# Audio.net
KiCad netlist of a schematic drawn in Altium Designer
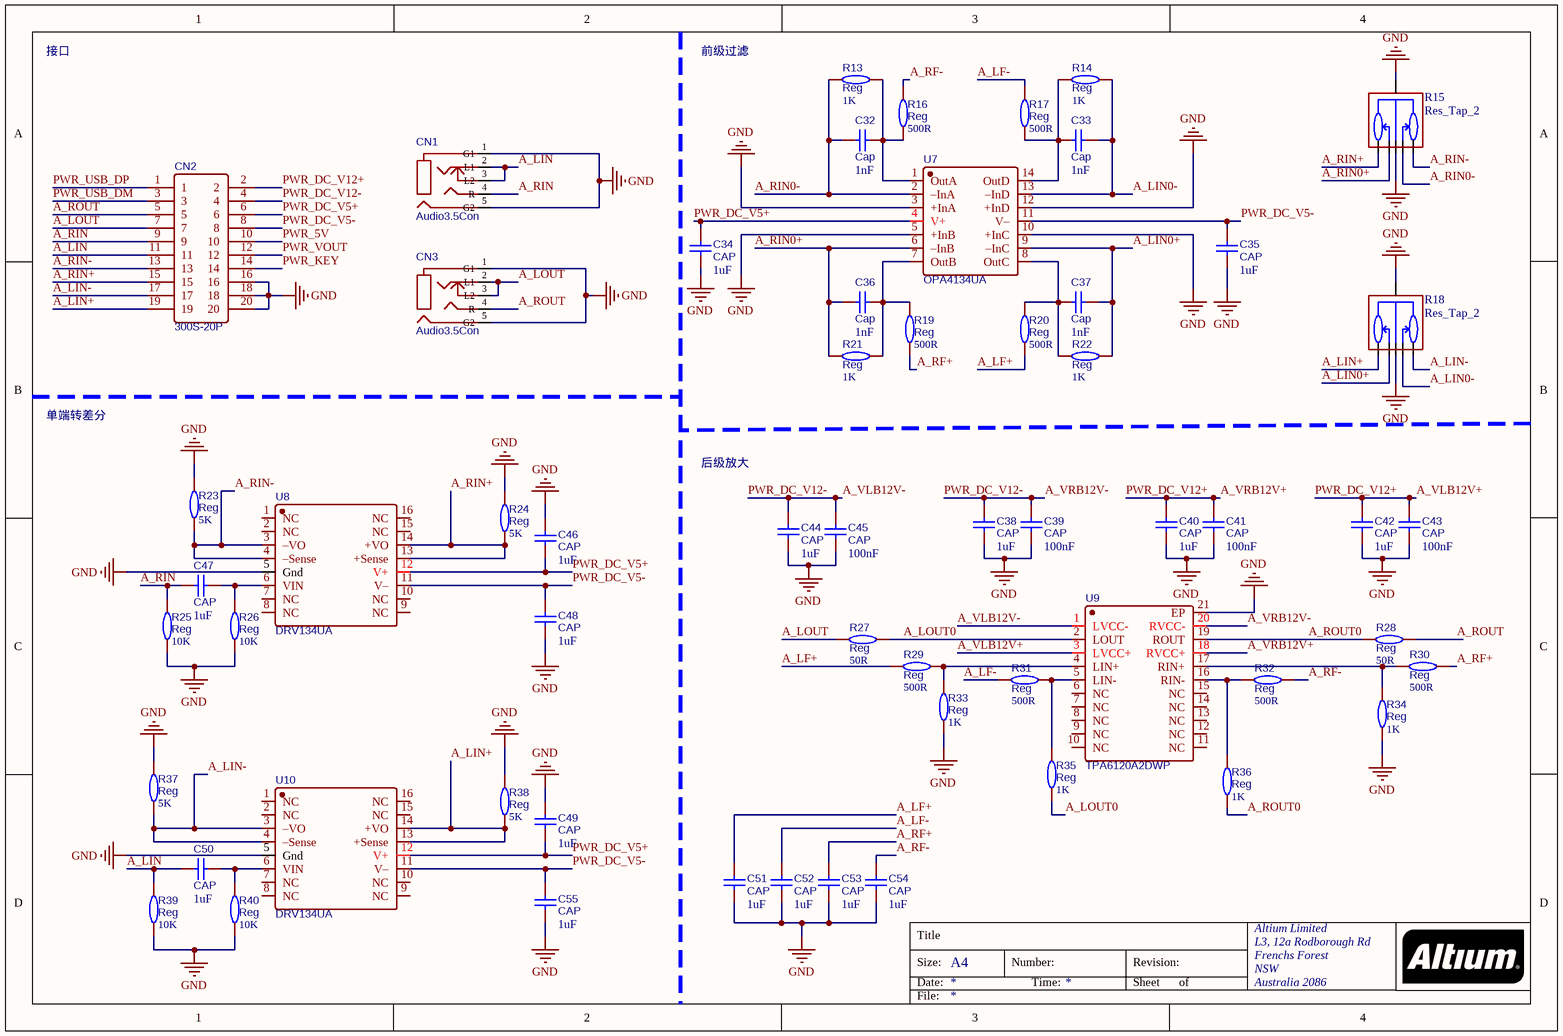
[diagram p0: Audio.SchDoc]

(export (version "E")
  (design (tool "Eeschema 10.0.6"))
  (components
    (comp (ref "C32")
      (value "Cap")
      (footprint "C0603")
      (fields
        (field (name "BOM_SUPPLIER PART") "C302008")
        (field (name "BOM_MANUFACTURER PART") "0603B103K101CT")
        (field (name "ALTIUM_VALUE") "1nF")
        (field (name "CONTRIBUTOR") "LCSC")
      )
      (libsource (lib "Levent_lib") (part "CAP"))
    )
    (comp (ref "C33")
      (value "Cap")
      (footprint "C0603")
      (fields
        (field (name "BOM_SUPPLIER PART") "C302008")
        (field (name "BOM_MANUFACTURER PART") "0603B103K101CT")
        (field (name "ALTIUM_VALUE") "1nF")
        (field (name "CONTRIBUTOR") "LCSC")
      )
      (libsource (lib "Levent_lib") (part "CAP"))
    )
    (comp (ref "C34")
      (value "CAP")
      (footprint "C0603")
      (description "Cap")
      (fields
        (field (name "BOM_SUPPLIER PART") "C302008")
        (field (name "BOM_MANUFACTURER PART") "0603B103K101CT")
        (field (name "ALTIUM_VALUE") "1uF")
        (field (name "CONTRIBUTOR") "LCSC")
      )
      (libsource (lib "Levent_lib") (part "CAP"))
    )
    (comp (ref "C35")
      (value "CAP")
      (footprint "C0603")
      (description "Cap")
      (fields
        (field (name "BOM_SUPPLIER PART") "C302008")
        (field (name "BOM_MANUFACTURER PART") "0603B103K101CT")
        (field (name "ALTIUM_VALUE") "1uF")
        (field (name "CONTRIBUTOR") "LCSC")
      )
      (libsource (lib "Levent_lib") (part "CAP"))
    )
    (comp (ref "C36")
      (value "Cap")
      (footprint "C0603")
      (fields
        (field (name "BOM_SUPPLIER PART") "C302008")
        (field (name "BOM_MANUFACTURER PART") "0603B103K101CT")
        (field (name "ALTIUM_VALUE") "1nF")
        (field (name "CONTRIBUTOR") "LCSC")
      )
      (libsource (lib "Levent_lib") (part "CAP"))
    )
    (comp (ref "C37")
      (value "Cap")
      (footprint "C0603")
      (fields
        (field (name "BOM_SUPPLIER PART") "C302008")
        (field (name "BOM_MANUFACTURER PART") "0603B103K101CT")
        (field (name "ALTIUM_VALUE") "1nF")
        (field (name "CONTRIBUTOR") "LCSC")
      )
      (libsource (lib "Levent_lib") (part "CAP"))
    )
    (comp (ref "C38")
      (value "CAP")
      (footprint "C0603")
      (description "Cap")
      (fields
        (field (name "BOM_SUPPLIER PART") "C302008")
        (field (name "BOM_MANUFACTURER PART") "0603B103K101CT")
        (field (name "ALTIUM_VALUE") "1uF")
        (field (name "CONTRIBUTOR") "LCSC")
      )
      (libsource (lib "Levent_lib") (part "CAP"))
    )
    (comp (ref "C39")
      (value "CAP")
      (footprint "C0603")
      (description "Cap")
      (fields
        (field (name "BOM_SUPPLIER PART") "C302008")
        (field (name "BOM_MANUFACTURER PART") "0603B103K101CT")
        (field (name "ALTIUM_VALUE") "100nF")
        (field (name "CONTRIBUTOR") "LCSC")
      )
      (libsource (lib "Levent_lib") (part "CAP"))
    )
    (comp (ref "C40")
      (value "CAP")
      (footprint "C0603")
      (description "Cap")
      (fields
        (field (name "BOM_SUPPLIER PART") "C302008")
        (field (name "BOM_MANUFACTURER PART") "0603B103K101CT")
        (field (name "ALTIUM_VALUE") "1uF")
        (field (name "CONTRIBUTOR") "LCSC")
      )
      (libsource (lib "Levent_lib") (part "CAP"))
    )
    (comp (ref "C41")
      (value "CAP")
      (footprint "C0603")
      (description "Cap")
      (fields
        (field (name "BOM_SUPPLIER PART") "C302008")
        (field (name "BOM_MANUFACTURER PART") "0603B103K101CT")
        (field (name "ALTIUM_VALUE") "100nF")
        (field (name "CONTRIBUTOR") "LCSC")
      )
      (libsource (lib "Levent_lib") (part "CAP"))
    )
    (comp (ref "C42")
      (value "CAP")
      (footprint "C0603")
      (description "Cap")
      (fields
        (field (name "BOM_SUPPLIER PART") "C302008")
        (field (name "BOM_MANUFACTURER PART") "0603B103K101CT")
        (field (name "ALTIUM_VALUE") "1uF")
        (field (name "CONTRIBUTOR") "LCSC")
      )
      (libsource (lib "Levent_lib") (part "CAP"))
    )
    (comp (ref "C43")
      (value "CAP")
      (footprint "C0603")
      (description "Cap")
      (fields
        (field (name "BOM_SUPPLIER PART") "C302008")
        (field (name "BOM_MANUFACTURER PART") "0603B103K101CT")
        (field (name "ALTIUM_VALUE") "100nF")
        (field (name "CONTRIBUTOR") "LCSC")
      )
      (libsource (lib "Levent_lib") (part "CAP"))
    )
    (comp (ref "C44")
      (value "CAP")
      (footprint "C0603")
      (description "Cap")
      (fields
        (field (name "BOM_SUPPLIER PART") "C302008")
        (field (name "BOM_MANUFACTURER PART") "0603B103K101CT")
        (field (name "ALTIUM_VALUE") "1uF")
        (field (name "CONTRIBUTOR") "LCSC")
      )
      (libsource (lib "Levent_lib") (part "CAP"))
    )
    (comp (ref "C45")
      (value "CAP")
      (footprint "C0603")
      (description "Cap")
      (fields
        (field (name "BOM_SUPPLIER PART") "C302008")
        (field (name "BOM_MANUFACTURER PART") "0603B103K101CT")
        (field (name "ALTIUM_VALUE") "100nF")
        (field (name "CONTRIBUTOR") "LCSC")
      )
      (libsource (lib "Levent_lib") (part "CAP"))
    )
    (comp (ref "C46")
      (value "CAP")
      (footprint "C0603")
      (description "Cap")
      (fields
        (field (name "BOM_SUPPLIER PART") "C302008")
        (field (name "BOM_MANUFACTURER PART") "0603B103K101CT")
        (field (name "ALTIUM_VALUE") "1uF")
        (field (name "CONTRIBUTOR") "LCSC")
      )
      (libsource (lib "Levent_lib") (part "CAP"))
    )
    (comp (ref "C47")
      (value "CAP")
      (footprint "C0603")
      (description "Cap")
      (fields
        (field (name "BOM_SUPPLIER PART") "C302008")
        (field (name "BOM_MANUFACTURER PART") "0603B103K101CT")
        (field (name "ALTIUM_VALUE") "1uF")
        (field (name "CONTRIBUTOR") "LCSC")
      )
      (libsource (lib "Levent_lib") (part "CAP"))
    )
    (comp (ref "C48")
      (value "CAP")
      (footprint "C0603")
      (description "Cap")
      (fields
        (field (name "BOM_SUPPLIER PART") "C302008")
        (field (name "BOM_MANUFACTURER PART") "0603B103K101CT")
        (field (name "ALTIUM_VALUE") "1uF")
        (field (name "CONTRIBUTOR") "LCSC")
      )
      (libsource (lib "Levent_lib") (part "CAP"))
    )
    (comp (ref "C49")
      (value "CAP")
      (footprint "C0603")
      (description "Cap")
      (fields
        (field (name "BOM_SUPPLIER PART") "C302008")
        (field (name "BOM_MANUFACTURER PART") "0603B103K101CT")
        (field (name "ALTIUM_VALUE") "1uF")
        (field (name "CONTRIBUTOR") "LCSC")
      )
      (libsource (lib "Levent_lib") (part "CAP"))
    )
    (comp (ref "C50")
      (value "CAP")
      (footprint "C0603")
      (description "Cap")
      (fields
        (field (name "BOM_SUPPLIER PART") "C302008")
        (field (name "BOM_MANUFACTURER PART") "0603B103K101CT")
        (field (name "ALTIUM_VALUE") "1uF")
        (field (name "CONTRIBUTOR") "LCSC")
      )
      (libsource (lib "Levent_lib") (part "CAP"))
    )
    (comp (ref "C51")
      (value "CAP")
      (footprint "C0603")
      (description "Cap")
      (fields
        (field (name "BOM_SUPPLIER PART") "C302008")
        (field (name "BOM_MANUFACTURER PART") "0603B103K101CT")
        (field (name "ALTIUM_VALUE") "1uF")
        (field (name "CONTRIBUTOR") "LCSC")
      )
      (libsource (lib "Levent_lib") (part "CAP"))
    )
    (comp (ref "C52")
      (value "CAP")
      (footprint "C0603")
      (description "Cap")
      (fields
        (field (name "BOM_SUPPLIER PART") "C302008")
        (field (name "BOM_MANUFACTURER PART") "0603B103K101CT")
        (field (name "ALTIUM_VALUE") "1uF")
        (field (name "CONTRIBUTOR") "LCSC")
      )
      (libsource (lib "Levent_lib") (part "CAP"))
    )
    (comp (ref "C53")
      (value "CAP")
      (footprint "C0603")
      (description "Cap")
      (fields
        (field (name "BOM_SUPPLIER PART") "C302008")
        (field (name "BOM_MANUFACTURER PART") "0603B103K101CT")
        (field (name "ALTIUM_VALUE") "1uF")
        (field (name "CONTRIBUTOR") "LCSC")
      )
      (libsource (lib "Levent_lib") (part "CAP"))
    )
    (comp (ref "C54")
      (value "CAP")
      (footprint "C0603")
      (description "Cap")
      (fields
        (field (name "BOM_SUPPLIER PART") "C302008")
        (field (name "BOM_MANUFACTURER PART") "0603B103K101CT")
        (field (name "ALTIUM_VALUE") "1uF")
        (field (name "CONTRIBUTOR") "LCSC")
      )
      (libsource (lib "Levent_lib") (part "CAP"))
    )
    (comp (ref "C55")
      (value "CAP")
      (footprint "C0603")
      (description "Cap")
      (fields
        (field (name "BOM_SUPPLIER PART") "C302008")
        (field (name "BOM_MANUFACTURER PART") "0603B103K101CT")
        (field (name "ALTIUM_VALUE") "1uF")
        (field (name "CONTRIBUTOR") "LCSC")
      )
      (libsource (lib "Levent_lib") (part "CAP"))
    )
    (comp (ref "CN1")
      (value "Audio3.5Con")
      (footprint "Audio3.5_3Pin")
      (description "3.5mm 3Pin 音频接口")
      (fields
        (field (name "BOM_SUPPLIER PART") "C2837065")
        (field (name "BOM_MANUFACTURER PART") "PJ-393")
        (field (name "CONTRIBUTOR") "LCSC")
      )
      (libsource (lib "Levent_lib") (part "AudioCon3"))
    )
    (comp (ref "CN2")
      (value "300S-20P")
      (footprint "DC_20P_2.54")
      (description "DC牛角座，20P")
      (fields (field (name "BOM_SUPPLIER PART") "C132442") (field (name "CONTRIBUTOR") "LCSC"))
      (libsource (lib "Levent_lib") (part "DC-20P"))
    )
    (comp (ref "CN3")
      (value "Audio3.5Con")
      (footprint "Audio3.5_3Pin")
      (description "3.5mm 3Pin 音频接口")
      (fields
        (field (name "BOM_SUPPLIER PART") "C2837065")
        (field (name "BOM_MANUFACTURER PART") "PJ-393")
        (field (name "CONTRIBUTOR") "LCSC")
      )
      (libsource (lib "Levent_lib") (part "AudioCon3"))
    )
    (comp (ref "R13")
      (value "Reg")
      (footprint "R0603")
      (description "电阻")
      (fields
        (field (name "BOM_SUPPLIER PART") "C465721")
        (field (name "BOM_MANUFACTURER PART") "AR03BTCX1002A")
        (field (name "ALTIUM_VALUE") "1K")
        (field (name "CONTRIBUTOR") "LCSC")
      )
      (libsource (lib "Levent_lib") (part "Res"))
    )
    (comp (ref "R14")
      (value "Reg")
      (footprint "R0603")
      (description "电阻")
      (fields
        (field (name "BOM_SUPPLIER PART") "C465721")
        (field (name "BOM_MANUFACTURER PART") "AR03BTCX1002A")
        (field (name "ALTIUM_VALUE") "1K")
        (field (name "CONTRIBUTOR") "LCSC")
      )
      (libsource (lib "Levent_lib") (part "Res"))
    )
    (comp (ref "R15")
      (value "Res_Tap_2")
      (footprint "RES_TAP_5Pin")
      (description "双联电位器")
      (libsource (lib "Levent_lib") (part "Res_Tap_2"))
    )
    (comp (ref "R16")
      (value "Reg")
      (footprint "R0603")
      (description "电阻")
      (fields
        (field (name "BOM_SUPPLIER PART") "C465721")
        (field (name "BOM_MANUFACTURER PART") "AR03BTCX1002A")
        (field (name "ALTIUM_VALUE") "500R")
        (field (name "CONTRIBUTOR") "LCSC")
      )
      (libsource (lib "Levent_lib") (part "Res"))
    )
    (comp (ref "R17")
      (value "Reg")
      (footprint "R0603")
      (description "电阻")
      (fields
        (field (name "BOM_SUPPLIER PART") "C465721")
        (field (name "BOM_MANUFACTURER PART") "AR03BTCX1002A")
        (field (name "ALTIUM_VALUE") "500R")
        (field (name "CONTRIBUTOR") "LCSC")
      )
      (libsource (lib "Levent_lib") (part "Res"))
    )
    (comp (ref "R18")
      (value "Res_Tap_2")
      (footprint "RES_TAP_5Pin")
      (description "双联电位器")
      (libsource (lib "Levent_lib") (part "Res_Tap_2"))
    )
    (comp (ref "R19")
      (value "Reg")
      (footprint "R0603")
      (description "电阻")
      (fields
        (field (name "BOM_SUPPLIER PART") "C465721")
        (field (name "BOM_MANUFACTURER PART") "AR03BTCX1002A")
        (field (name "ALTIUM_VALUE") "500R")
        (field (name "CONTRIBUTOR") "LCSC")
      )
      (libsource (lib "Levent_lib") (part "Res"))
    )
    (comp (ref "R20")
      (value "Reg")
      (footprint "R0603")
      (description "电阻")
      (fields
        (field (name "BOM_SUPPLIER PART") "C465721")
        (field (name "BOM_MANUFACTURER PART") "AR03BTCX1002A")
        (field (name "ALTIUM_VALUE") "500R")
        (field (name "CONTRIBUTOR") "LCSC")
      )
      (libsource (lib "Levent_lib") (part "Res"))
    )
    (comp (ref "R21")
      (value "Reg")
      (footprint "R0603")
      (description "电阻")
      (fields
        (field (name "BOM_SUPPLIER PART") "C465721")
        (field (name "BOM_MANUFACTURER PART") "AR03BTCX1002A")
        (field (name "ALTIUM_VALUE") "1K")
        (field (name "CONTRIBUTOR") "LCSC")
      )
      (libsource (lib "Levent_lib") (part "Res"))
    )
    (comp (ref "R22")
      (value "Reg")
      (footprint "R0603")
      (description "电阻")
      (fields
        (field (name "BOM_SUPPLIER PART") "C465721")
        (field (name "BOM_MANUFACTURER PART") "AR03BTCX1002A")
        (field (name "ALTIUM_VALUE") "1K")
        (field (name "CONTRIBUTOR") "LCSC")
      )
      (libsource (lib "Levent_lib") (part "Res"))
    )
    (comp (ref "R23")
      (value "Reg")
      (footprint "R0603")
      (description "电阻")
      (fields
        (field (name "BOM_SUPPLIER PART") "C465721")
        (field (name "BOM_MANUFACTURER PART") "AR03BTCX1002A")
        (field (name "ALTIUM_VALUE") "5K")
        (field (name "CONTRIBUTOR") "LCSC")
      )
      (libsource (lib "Levent_lib") (part "Res"))
    )
    (comp (ref "R24")
      (value "Reg")
      (footprint "R0603")
      (description "电阻")
      (fields
        (field (name "BOM_SUPPLIER PART") "C465721")
        (field (name "BOM_MANUFACTURER PART") "AR03BTCX1002A")
        (field (name "ALTIUM_VALUE") "5K")
        (field (name "CONTRIBUTOR") "LCSC")
      )
      (libsource (lib "Levent_lib") (part "Res"))
    )
    (comp (ref "R25")
      (value "Reg")
      (footprint "R0603")
      (description "电阻")
      (fields
        (field (name "BOM_SUPPLIER PART") "C465721")
        (field (name "BOM_MANUFACTURER PART") "AR03BTCX1002A")
        (field (name "ALTIUM_VALUE") "10K")
        (field (name "CONTRIBUTOR") "LCSC")
      )
      (libsource (lib "Levent_lib") (part "Res"))
    )
    (comp (ref "R26")
      (value "Reg")
      (footprint "R0603")
      (description "电阻")
      (fields
        (field (name "BOM_SUPPLIER PART") "C465721")
        (field (name "BOM_MANUFACTURER PART") "AR03BTCX1002A")
        (field (name "ALTIUM_VALUE") "10K")
        (field (name "CONTRIBUTOR") "LCSC")
      )
      (libsource (lib "Levent_lib") (part "Res"))
    )
    (comp (ref "R27")
      (value "Reg")
      (footprint "R0603")
      (description "电阻")
      (fields
        (field (name "BOM_SUPPLIER PART") "C465721")
        (field (name "BOM_MANUFACTURER PART") "AR03BTCX1002A")
        (field (name "ALTIUM_VALUE") "50R")
        (field (name "CONTRIBUTOR") "LCSC")
      )
      (libsource (lib "Levent_lib") (part "Res"))
    )
    (comp (ref "R28")
      (value "Reg")
      (footprint "R0603")
      (description "电阻")
      (fields
        (field (name "BOM_SUPPLIER PART") "C465721")
        (field (name "BOM_MANUFACTURER PART") "AR03BTCX1002A")
        (field (name "ALTIUM_VALUE") "50R")
        (field (name "CONTRIBUTOR") "LCSC")
      )
      (libsource (lib "Levent_lib") (part "Res"))
    )
    (comp (ref "R29")
      (value "Reg")
      (footprint "R0603")
      (description "电阻")
      (fields
        (field (name "BOM_SUPPLIER PART") "C465721")
        (field (name "BOM_MANUFACTURER PART") "AR03BTCX1002A")
        (field (name "ALTIUM_VALUE") "500R")
        (field (name "CONTRIBUTOR") "LCSC")
      )
      (libsource (lib "Levent_lib") (part "Res"))
    )
    (comp (ref "R30")
      (value "Reg")
      (footprint "R0603")
      (description "电阻")
      (fields
        (field (name "BOM_SUPPLIER PART") "C465721")
        (field (name "BOM_MANUFACTURER PART") "AR03BTCX1002A")
        (field (name "ALTIUM_VALUE") "500R")
        (field (name "CONTRIBUTOR") "LCSC")
      )
      (libsource (lib "Levent_lib") (part "Res"))
    )
    (comp (ref "R31")
      (value "Reg")
      (footprint "R0603")
      (description "电阻")
      (fields
        (field (name "BOM_SUPPLIER PART") "C465721")
        (field (name "BOM_MANUFACTURER PART") "AR03BTCX1002A")
        (field (name "ALTIUM_VALUE") "500R")
        (field (name "CONTRIBUTOR") "LCSC")
      )
      (libsource (lib "Levent_lib") (part "Res"))
    )
    (comp (ref "R32")
      (value "Reg")
      (footprint "R0603")
      (description "电阻")
      (fields
        (field (name "BOM_SUPPLIER PART") "C465721")
        (field (name "BOM_MANUFACTURER PART") "AR03BTCX1002A")
        (field (name "ALTIUM_VALUE") "500R")
        (field (name "CONTRIBUTOR") "LCSC")
      )
      (libsource (lib "Levent_lib") (part "Res"))
    )
    (comp (ref "R33")
      (value "Reg")
      (footprint "R0603")
      (description "电阻")
      (fields
        (field (name "BOM_SUPPLIER PART") "C465721")
        (field (name "BOM_MANUFACTURER PART") "AR03BTCX1002A")
        (field (name "ALTIUM_VALUE") "1K")
        (field (name "CONTRIBUTOR") "LCSC")
      )
      (libsource (lib "Levent_lib") (part "Res"))
    )
    (comp (ref "R34")
      (value "Reg")
      (footprint "R0603")
      (description "电阻")
      (fields
        (field (name "BOM_SUPPLIER PART") "C465721")
        (field (name "BOM_MANUFACTURER PART") "AR03BTCX1002A")
        (field (name "ALTIUM_VALUE") "1K")
        (field (name "CONTRIBUTOR") "LCSC")
      )
      (libsource (lib "Levent_lib") (part "Res"))
    )
    (comp (ref "R35")
      (value "Reg")
      (footprint "R0603")
      (description "电阻")
      (fields
        (field (name "BOM_SUPPLIER PART") "C465721")
        (field (name "BOM_MANUFACTURER PART") "AR03BTCX1002A")
        (field (name "ALTIUM_VALUE") "1K")
        (field (name "CONTRIBUTOR") "LCSC")
      )
      (libsource (lib "Levent_lib") (part "Res"))
    )
    (comp (ref "R36")
      (value "Reg")
      (footprint "R0603")
      (description "电阻")
      (fields
        (field (name "BOM_SUPPLIER PART") "C465721")
        (field (name "BOM_MANUFACTURER PART") "AR03BTCX1002A")
        (field (name "ALTIUM_VALUE") "1K")
        (field (name "CONTRIBUTOR") "LCSC")
      )
      (libsource (lib "Levent_lib") (part "Res"))
    )
    (comp (ref "R37")
      (value "Reg")
      (footprint "R0603")
      (description "电阻")
      (fields
        (field (name "BOM_SUPPLIER PART") "C465721")
        (field (name "BOM_MANUFACTURER PART") "AR03BTCX1002A")
        (field (name "ALTIUM_VALUE") "5K")
        (field (name "CONTRIBUTOR") "LCSC")
      )
      (libsource (lib "Levent_lib") (part "Res"))
    )
    (comp (ref "R38")
      (value "Reg")
      (footprint "R0603")
      (description "电阻")
      (fields
        (field (name "BOM_SUPPLIER PART") "C465721")
        (field (name "BOM_MANUFACTURER PART") "AR03BTCX1002A")
        (field (name "ALTIUM_VALUE") "5K")
        (field (name "CONTRIBUTOR") "LCSC")
      )
      (libsource (lib "Levent_lib") (part "Res"))
    )
    (comp (ref "R39")
      (value "Reg")
      (footprint "R0603")
      (description "电阻")
      (fields
        (field (name "BOM_SUPPLIER PART") "C465721")
        (field (name "BOM_MANUFACTURER PART") "AR03BTCX1002A")
        (field (name "ALTIUM_VALUE") "10K")
        (field (name "CONTRIBUTOR") "LCSC")
      )
      (libsource (lib "Levent_lib") (part "Res"))
    )
    (comp (ref "R40")
      (value "Reg")
      (footprint "R0603")
      (description "电阻")
      (fields
        (field (name "BOM_SUPPLIER PART") "C465721")
        (field (name "BOM_MANUFACTURER PART") "AR03BTCX1002A")
        (field (name "ALTIUM_VALUE") "10K")
        (field (name "CONTRIBUTOR") "LCSC")
      )
      (libsource (lib "Levent_lib") (part "Res"))
    )
    (comp (ref "U7")
      (value "OPA4134UA")
      (footprint "SOIC-16_5.4mm")
      (description "耳放")
      (fields (field (name "BOM_SUPPLIER PART") "C2832240") (field (name "CONTRIBUTOR") "LCSC"))
      (libsource (lib "Levent_lib") (part "OPA4134UA"))
    )
    (comp (ref "U8")
      (value "DRV134UA")
      (footprint "SOIC-16_9.5mm")
      (description "音频差分放大器")
      (fields (field (name "BOM_SUPPLIER PART") "C1519988") (field (name "CONTRIBUTOR") "LCSC"))
      (libsource (lib "Levent_lib") (part "DRV134UA"))
    )
    (comp (ref "U9")
      (value "TPA6120A2DWP")
      (footprint "HSOP-20")
      (description "耳放")
      (fields (field (name "BOM_SUPPLIER PART") "C2871054") (field (name "CONTRIBUTOR") "LCSC"))
      (libsource (lib "Levent_lib") (part "TPA6120"))
    )
    (comp (ref "U10")
      (value "DRV134UA")
      (footprint "SOIC-16_9.5mm")
      (description "音频差分放大器")
      (fields (field (name "BOM_SUPPLIER PART") "C1519988") (field (name "CONTRIBUTOR") "LCSC"))
      (libsource (lib "Levent_lib") (part "DRV134UA"))
    )
  )
  (nets
    (net (code "1") (name "/A_LF+") (class "Default")
      (node (ref "C51") (pin "1") (pinfunction "1_1") (pintype "passive"))
      (node (ref "R20") (pin "1") (pinfunction "1_1") (pintype "passive"))
      (node (ref "R29") (pin "1") (pinfunction "1_1") (pintype "passive"))
    )
    (net (code "2") (name "/A_LF-") (class "Default")
      (node (ref "C52") (pin "1") (pinfunction "1_1") (pintype "passive"))
      (node (ref "R17") (pin "2") (pinfunction "2_2") (pintype "passive"))
      (node (ref "R31") (pin "1") (pinfunction "1_1") (pintype "passive"))
    )
    (net (code "3") (name "/A_LIN") (class "Default")
      (node (ref "C50") (pin "1") (pinfunction "1_1") (pintype "passive"))
      (node (ref "CN1") (pin "2") (pinfunction "L1_2") (pintype "passive"))
      (node (ref "CN1") (pin "3") (pinfunction "L2_3") (pintype "passive"))
      (node (ref "CN2") (pin "11") (pinfunction "11_11") (pintype "passive"))
      (node (ref "R39") (pin "2") (pinfunction "2_2") (pintype "passive"))
    )
    (net (code "4") (name "/A_LIN+") (class "Default")
      (node (ref "CN2") (pin "19") (pinfunction "19_19") (pintype "passive"))
      (node (ref "R18") (pin "4") (pinfunction "CH2B_4") (pintype "passive"))
      (node (ref "R38") (pin "2") (pinfunction "2_2") (pintype "passive"))
      (node (ref "U10") (pin "13") (pinfunction "+Sense_13") (pintype "passive"))
      (node (ref "U10") (pin "14") (pinfunction "+VO_14") (pintype "passive"))
    )
    (net (code "5") (name "/A_LIN-") (class "Default")
      (node (ref "CN2") (pin "17") (pinfunction "17_17") (pintype "passive"))
      (node (ref "R18") (pin "5") (pinfunction "CH1B_5") (pintype "passive"))
      (node (ref "R37") (pin "1") (pinfunction "1_1") (pintype "passive"))
      (node (ref "U10") (pin "3") (pinfunction "–VO_3") (pintype "passive"))
      (node (ref "U10") (pin "4") (pinfunction "–Sense_4") (pintype "passive"))
    )
    (net (code "6") (name "/A_LIN0+") (class "Default")
      (node (ref "C37") (pin "2") (pinfunction "2_2") (pintype "passive"))
      (node (ref "R18") (pin "3") (pinfunction "CH2A_3") (pintype "passive"))
      (node (ref "R22") (pin "2") (pinfunction "2_2") (pintype "passive"))
      (node (ref "U7") (pin "9") (pinfunction "–InC_9") (pintype "passive"))
    )
    (net (code "7") (name "/A_LIN0-") (class "Default")
      (node (ref "C33") (pin "2") (pinfunction "2_2") (pintype "passive"))
      (node (ref "R14") (pin "2") (pinfunction "2_2") (pintype "passive"))
      (node (ref "R18") (pin "2") (pinfunction "CH1A_2") (pintype "passive"))
      (node (ref "U7") (pin "13") (pinfunction "–InD_13") (pintype "passive"))
    )
    (net (code "8") (name "/A_LOUT") (class "Default")
      (node (ref "CN2") (pin "7") (pinfunction "7_7") (pintype "passive"))
      (node (ref "CN3") (pin "2") (pinfunction "L1_2") (pintype "passive"))
      (node (ref "CN3") (pin "3") (pinfunction "L2_3") (pintype "passive"))
      (node (ref "R27") (pin "1") (pinfunction "1_1") (pintype "passive"))
    )
    (net (code "9") (name "/A_LOUT0") (class "Default")
      (node (ref "R27") (pin "2") (pinfunction "2_2") (pintype "passive"))
      (node (ref "R35") (pin "1") (pinfunction "1_1") (pintype "passive"))
      (node (ref "U9") (pin "2") (pinfunction "LOUT_2") (pintype "passive"))
    )
    (net (code "10") (name "/A_RF+") (class "Default")
      (node (ref "C53") (pin "1") (pinfunction "1_1") (pintype "passive"))
      (node (ref "R19") (pin "1") (pinfunction "1_1") (pintype "passive"))
      (node (ref "R30") (pin "1") (pinfunction "1_1") (pintype "passive"))
    )
    (net (code "11") (name "/A_RF-") (class "Default")
      (node (ref "C54") (pin "1") (pinfunction "1_1") (pintype "passive"))
      (node (ref "R16") (pin "2") (pinfunction "2_2") (pintype "passive"))
      (node (ref "R32") (pin "1") (pinfunction "1_1") (pintype "passive"))
    )
    (net (code "12") (name "/A_RIN") (class "Default")
      (node (ref "C47") (pin "1") (pinfunction "1_1") (pintype "passive"))
      (node (ref "CN1") (pin "4") (pinfunction "R_4") (pintype "passive"))
      (node (ref "CN2") (pin "9") (pinfunction "9_9") (pintype "passive"))
      (node (ref "R25") (pin "2") (pinfunction "2_2") (pintype "passive"))
    )
    (net (code "13") (name "/A_RIN+") (class "Default")
      (node (ref "CN2") (pin "15") (pinfunction "15_15") (pintype "passive"))
      (node (ref "R15") (pin "4") (pinfunction "CH2B_4") (pintype "passive"))
      (node (ref "R24") (pin "2") (pinfunction "2_2") (pintype "passive"))
      (node (ref "U8") (pin "13") (pinfunction "+Sense_13") (pintype "passive"))
      (node (ref "U8") (pin "14") (pinfunction "+VO_14") (pintype "passive"))
    )
    (net (code "14") (name "/A_RIN-") (class "Default")
      (node (ref "CN2") (pin "13") (pinfunction "13_13") (pintype "passive"))
      (node (ref "R15") (pin "5") (pinfunction "CH1B_5") (pintype "passive"))
      (node (ref "R23") (pin "1") (pinfunction "1_1") (pintype "passive"))
      (node (ref "U8") (pin "3") (pinfunction "–VO_3") (pintype "passive"))
      (node (ref "U8") (pin "4") (pinfunction "–Sense_4") (pintype "passive"))
    )
    (net (code "15") (name "/A_RIN0+") (class "Default")
      (node (ref "C36") (pin "1") (pinfunction "1_1") (pintype "passive"))
      (node (ref "R15") (pin "3") (pinfunction "CH2A_3") (pintype "passive"))
      (node (ref "R21") (pin "1") (pinfunction "1_1") (pintype "passive"))
      (node (ref "U7") (pin "6") (pinfunction "–InB_6") (pintype "passive"))
    )
    (net (code "16") (name "/A_RIN0-") (class "Default")
      (node (ref "C32") (pin "1") (pinfunction "1_1") (pintype "passive"))
      (node (ref "R13") (pin "1") (pinfunction "1_1") (pintype "passive"))
      (node (ref "R15") (pin "2") (pinfunction "CH1A_2") (pintype "passive"))
      (node (ref "U7") (pin "2") (pinfunction "–InA_2") (pintype "passive"))
    )
    (net (code "17") (name "/A_ROUT") (class "Default")
      (node (ref "CN2") (pin "5") (pinfunction "5_5") (pintype "passive"))
      (node (ref "CN3") (pin "4") (pinfunction "R_4") (pintype "passive"))
      (node (ref "R28") (pin "2") (pinfunction "2_2") (pintype "passive"))
    )
    (net (code "18") (name "/A_ROUT0") (class "Default")
      (node (ref "R28") (pin "1") (pinfunction "1_1") (pintype "passive"))
      (node (ref "R36") (pin "1") (pinfunction "1_1") (pintype "passive"))
      (node (ref "U9") (pin "19") (pinfunction "ROUT_19") (pintype "passive"))
    )
    (net (code "19") (name "/A_VLB12V+") (class "Default")
      (node (ref "C40") (pin "2") (pinfunction "2_2") (pintype "passive"))
      (node (ref "C41") (pin "2") (pinfunction "2_2") (pintype "passive"))
      (node (ref "C42") (pin "2") (pinfunction "2_2") (pintype "passive"))
      (node (ref "C43") (pin "2") (pinfunction "2_2") (pintype "passive"))
      (node (ref "CN2") (pin "2") (pinfunction "2_2") (pintype "passive"))
      (node (ref "U9") (pin "18") (pinfunction "RVCC+_18") (pintype "passive"))
      (node (ref "U9") (pin "3") (pinfunction "LVCC+_3") (pintype "passive"))
    )
    (net (code "20") (name "/A_VLB12V-") (class "Default")
      (node (ref "C38") (pin "2") (pinfunction "2_2") (pintype "passive"))
      (node (ref "C39") (pin "2") (pinfunction "2_2") (pintype "passive"))
      (node (ref "C44") (pin "2") (pinfunction "2_2") (pintype "passive"))
      (node (ref "C45") (pin "2") (pinfunction "2_2") (pintype "passive"))
      (node (ref "CN2") (pin "4") (pinfunction "4_4") (pintype "passive"))
      (node (ref "U9") (pin "1") (pinfunction "LVCC-_1") (pintype "passive"))
      (node (ref "U9") (pin "20") (pinfunction "RVCC-_20") (pintype "passive"))
    )
    (net (code "21") (name "/PWR_5V") (class "Default")
      (node (ref "CN2") (pin "10") (pinfunction "10_10") (pintype "passive"))
    )
    (net (code "22") (name "/PWR_DC_V5+") (class "Default")
      (node (ref "C34") (pin "2") (pinfunction "2_2") (pintype "passive"))
      (node (ref "C46") (pin "1") (pinfunction "1_1") (pintype "passive"))
      (node (ref "C49") (pin "1") (pinfunction "1_1") (pintype "passive"))
      (node (ref "CN2") (pin "6") (pinfunction "6_6") (pintype "passive"))
      (node (ref "U10") (pin "12") (pinfunction "V+_12") (pintype "passive"))
      (node (ref "U7") (pin "4") (pinfunction "V+_4") (pintype "passive"))
      (node (ref "U8") (pin "12") (pinfunction "V+_12") (pintype "passive"))
    )
    (net (code "23") (name "/PWR_DC_V5-") (class "Default")
      (node (ref "C35") (pin "2") (pinfunction "2_2") (pintype "passive"))
      (node (ref "C48") (pin "2") (pinfunction "2_2") (pintype "passive"))
      (node (ref "C55") (pin "2") (pinfunction "2_2") (pintype "passive"))
      (node (ref "CN2") (pin "8") (pinfunction "8_8") (pintype "passive"))
      (node (ref "U10") (pin "11") (pinfunction "V–_11") (pintype "passive"))
      (node (ref "U7") (pin "11") (pinfunction "V–_11") (pintype "passive"))
      (node (ref "U8") (pin "11") (pinfunction "V–_11") (pintype "passive"))
    )
    (net (code "24") (name "/PWR_KEY") (class "Default")
      (node (ref "CN2") (pin "14") (pinfunction "14_14") (pintype "passive"))
    )
    (net (code "25") (name "/PWR_USB_DM") (class "Default")
      (node (ref "CN2") (pin "3") (pinfunction "3_3") (pintype "passive"))
    )
    (net (code "26") (name "/PWR_USB_DP") (class "Default")
      (node (ref "CN2") (pin "1") (pinfunction "1_1") (pintype "passive"))
    )
    (net (code "27") (name "/PWR_VOUT") (class "Default")
      (node (ref "CN2") (pin "12") (pinfunction "12_12") (pintype "passive"))
    )
    (net (code "28") (name "GND") (class "Default")
      (node (ref "C34") (pin "1") (pinfunction "1_1") (pintype "passive"))
      (node (ref "C35") (pin "1") (pinfunction "1_1") (pintype "passive"))
      (node (ref "C38") (pin "1") (pinfunction "1_1") (pintype "passive"))
      (node (ref "C39") (pin "1") (pinfunction "1_1") (pintype "passive"))
      (node (ref "C40") (pin "1") (pinfunction "1_1") (pintype "passive"))
      (node (ref "C41") (pin "1") (pinfunction "1_1") (pintype "passive"))
      (node (ref "C42") (pin "1") (pinfunction "1_1") (pintype "passive"))
      (node (ref "C43") (pin "1") (pinfunction "1_1") (pintype "passive"))
      (node (ref "C44") (pin "1") (pinfunction "1_1") (pintype "passive"))
      (node (ref "C45") (pin "1") (pinfunction "1_1") (pintype "passive"))
      (node (ref "C46") (pin "2") (pinfunction "2_2") (pintype "passive"))
      (node (ref "C48") (pin "1") (pinfunction "1_1") (pintype "passive"))
      (node (ref "C49") (pin "2") (pinfunction "2_2") (pintype "passive"))
      (node (ref "C51") (pin "2") (pinfunction "2_2") (pintype "passive"))
      (node (ref "C52") (pin "2") (pinfunction "2_2") (pintype "passive"))
      (node (ref "C53") (pin "2") (pinfunction "2_2") (pintype "passive"))
      (node (ref "C54") (pin "2") (pinfunction "2_2") (pintype "passive"))
      (node (ref "C55") (pin "1") (pinfunction "1_1") (pintype "passive"))
      (node (ref "CN1") (pin "1") (pinfunction "G1_1") (pintype "passive"))
      (node (ref "CN1") (pin "5") (pinfunction "G2_5") (pintype "passive"))
      (node (ref "CN2") (pin "16") (pinfunction "16_16") (pintype "passive"))
      (node (ref "CN2") (pin "18") (pinfunction "18_18") (pintype "passive"))
      (node (ref "CN2") (pin "20") (pinfunction "20_20") (pintype "passive"))
      (node (ref "CN3") (pin "1") (pinfunction "G1_1") (pintype "passive"))
      (node (ref "CN3") (pin "5") (pinfunction "G2_5") (pintype "passive"))
      (node (ref "R15") (pin "1") (pinfunction "G_1") (pintype "passive"))
      (node (ref "R15") (pin "6") (pinfunction "PAD_6") (pintype "passive"))
      (node (ref "R18") (pin "1") (pinfunction "G_1") (pintype "passive"))
      (node (ref "R18") (pin "6") (pinfunction "PAD_6") (pintype "passive"))
      (node (ref "R23") (pin "2") (pinfunction "2_2") (pintype "passive"))
      (node (ref "R24") (pin "1") (pinfunction "1_1") (pintype "passive"))
      (node (ref "R25") (pin "1") (pinfunction "1_1") (pintype "passive"))
      (node (ref "R26") (pin "1") (pinfunction "1_1") (pintype "passive"))
      (node (ref "R33") (pin "1") (pinfunction "1_1") (pintype "passive"))
      (node (ref "R34") (pin "1") (pinfunction "1_1") (pintype "passive"))
      (node (ref "R37") (pin "2") (pinfunction "2_2") (pintype "passive"))
      (node (ref "R38") (pin "1") (pinfunction "1_1") (pintype "passive"))
      (node (ref "R39") (pin "1") (pinfunction "1_1") (pintype "passive"))
      (node (ref "R40") (pin "1") (pinfunction "1_1") (pintype "passive"))
      (node (ref "U10") (pin "5") (pinfunction "Gnd_5") (pintype "passive"))
      (node (ref "U7") (pin "10") (pinfunction "+InC_10") (pintype "passive"))
      (node (ref "U7") (pin "12") (pinfunction "+InD_12") (pintype "passive"))
      (node (ref "U7") (pin "3") (pinfunction "+InA_3") (pintype "passive"))
      (node (ref "U7") (pin "5") (pinfunction "+InB_5") (pintype "passive"))
      (node (ref "U8") (pin "5") (pinfunction "Gnd_5") (pintype "passive"))
      (node (ref "U9") (pin "21") (pinfunction "EP_21") (pintype "passive"))
    )
    (net (code "29") (name "Net-(U7-OutA)") (class "Default")
      (node (ref "C32") (pin "2") (pinfunction "2_2") (pintype "passive"))
      (node (ref "R13") (pin "2") (pinfunction "2_2") (pintype "passive"))
      (node (ref "R16") (pin "1") (pinfunction "1_1") (pintype "passive"))
      (node (ref "U7") (pin "1") (pinfunction "OutA_1") (pintype "passive"))
    )
    (net (code "30") (name "Net-(U7-OutB)") (class "Default")
      (node (ref "C36") (pin "2") (pinfunction "2_2") (pintype "passive"))
      (node (ref "R19") (pin "2") (pinfunction "2_2") (pintype "passive"))
      (node (ref "R21") (pin "2") (pinfunction "2_2") (pintype "passive"))
      (node (ref "U7") (pin "7") (pinfunction "OutB_7") (pintype "passive"))
    )
    (net (code "31") (name "Net-(U7-OutC)") (class "Default")
      (node (ref "C37") (pin "1") (pinfunction "1_1") (pintype "passive"))
      (node (ref "R20") (pin "2") (pinfunction "2_2") (pintype "passive"))
      (node (ref "R22") (pin "1") (pinfunction "1_1") (pintype "passive"))
      (node (ref "U7") (pin "8") (pinfunction "OutC_8") (pintype "passive"))
    )
    (net (code "32") (name "Net-(U7-OutD)") (class "Default")
      (node (ref "C33") (pin "1") (pinfunction "1_1") (pintype "passive"))
      (node (ref "R14") (pin "1") (pinfunction "1_1") (pintype "passive"))
      (node (ref "R17") (pin "1") (pinfunction "1_1") (pintype "passive"))
      (node (ref "U7") (pin "14") (pinfunction "OutD_14") (pintype "passive"))
    )
    (net (code "33") (name "Net-(U8-VIN)") (class "Default")
      (node (ref "C47") (pin "2") (pinfunction "2_2") (pintype "passive"))
      (node (ref "R26") (pin "2") (pinfunction "2_2") (pintype "passive"))
      (node (ref "U8") (pin "6") (pinfunction "VIN_6") (pintype "passive"))
    )
    (net (code "34") (name "Net-(U9-LIN+)") (class "Default")
      (node (ref "R29") (pin "2") (pinfunction "2_2") (pintype "passive"))
      (node (ref "R33") (pin "2") (pinfunction "2_2") (pintype "passive"))
      (node (ref "U9") (pin "4") (pinfunction "LIN+_4") (pintype "passive"))
    )
    (net (code "35") (name "Net-(U9-LIN-)") (class "Default")
      (node (ref "R31") (pin "2") (pinfunction "2_2") (pintype "passive"))
      (node (ref "R35") (pin "2") (pinfunction "2_2") (pintype "passive"))
      (node (ref "U9") (pin "5") (pinfunction "LIN-_5") (pintype "passive"))
    )
    (net (code "36") (name "Net-(U9-RIN+)") (class "Default")
      (node (ref "R30") (pin "2") (pinfunction "2_2") (pintype "passive"))
      (node (ref "R34") (pin "2") (pinfunction "2_2") (pintype "passive"))
      (node (ref "U9") (pin "17") (pinfunction "RIN+_17") (pintype "passive"))
    )
    (net (code "37") (name "Net-(U9-RIN-)") (class "Default")
      (node (ref "R32") (pin "2") (pinfunction "2_2") (pintype "passive"))
      (node (ref "R36") (pin "2") (pinfunction "2_2") (pintype "passive"))
      (node (ref "U9") (pin "16") (pinfunction "RIN-_16") (pintype "passive"))
    )
    (net (code "38") (name "Net-(U10-VIN)") (class "Default")
      (node (ref "C50") (pin "2") (pinfunction "2_2") (pintype "passive"))
      (node (ref "R40") (pin "2") (pinfunction "2_2") (pintype "passive"))
      (node (ref "U10") (pin "6") (pinfunction "VIN_6") (pintype "passive"))
    )
    (net (code "39") (name "unconnected-(U8-NC-Pad1)") (class "Default")
      (node (ref "U8") (pin "1") (pinfunction "NC_1") (pintype "passive"))
    )
    (net (code "40") (name "unconnected-(U8-NC-Pad2)") (class "Default")
      (node (ref "U8") (pin "2") (pinfunction "NC_2") (pintype "passive"))
    )
    (net (code "41") (name "unconnected-(U8-NC-Pad7)") (class "Default")
      (node (ref "U8") (pin "7") (pinfunction "NC_7") (pintype "passive"))
    )
    (net (code "42") (name "unconnected-(U8-NC-Pad8)") (class "Default")
      (node (ref "U8") (pin "8") (pinfunction "NC_8") (pintype "passive"))
    )
    (net (code "43") (name "unconnected-(U8-NC-Pad9)") (class "Default")
      (node (ref "U8") (pin "9") (pinfunction "NC_9") (pintype "passive"))
    )
    (net (code "44") (name "unconnected-(U8-NC-Pad10)") (class "Default")
      (node (ref "U8") (pin "10") (pinfunction "NC_10") (pintype "passive"))
    )
    (net (code "45") (name "unconnected-(U8-NC-Pad15)") (class "Default")
      (node (ref "U8") (pin "15") (pinfunction "NC_15") (pintype "passive"))
    )
    (net (code "46") (name "unconnected-(U8-NC-Pad16)") (class "Default")
      (node (ref "U8") (pin "16") (pinfunction "NC_16") (pintype "passive"))
    )
    (net (code "47") (name "unconnected-(U9-NC-Pad6)") (class "Default")
      (node (ref "U9") (pin "6") (pinfunction "NC_6") (pintype "passive"))
    )
    (net (code "48") (name "unconnected-(U9-NC-Pad7)") (class "Default")
      (node (ref "U9") (pin "7") (pinfunction "NC_7") (pintype "passive"))
    )
    (net (code "49") (name "unconnected-(U9-NC-Pad8)") (class "Default")
      (node (ref "U9") (pin "8") (pinfunction "NC_8") (pintype "passive"))
    )
    (net (code "50") (name "unconnected-(U9-NC-Pad9)") (class "Default")
      (node (ref "U9") (pin "9") (pinfunction "NC_9") (pintype "passive"))
    )
    (net (code "51") (name "unconnected-(U9-NC-Pad10)") (class "Default")
      (node (ref "U9") (pin "10") (pinfunction "NC_10") (pintype "passive"))
    )
    (net (code "52") (name "unconnected-(U9-NC-Pad11)") (class "Default")
      (node (ref "U9") (pin "11") (pinfunction "NC_11") (pintype "passive"))
    )
    (net (code "53") (name "unconnected-(U9-NC-Pad12)") (class "Default")
      (node (ref "U9") (pin "12") (pinfunction "NC_12") (pintype "passive"))
    )
    (net (code "54") (name "unconnected-(U9-NC-Pad13)") (class "Default")
      (node (ref "U9") (pin "13") (pinfunction "NC_13") (pintype "passive"))
    )
    (net (code "55") (name "unconnected-(U9-NC-Pad14)") (class "Default")
      (node (ref "U9") (pin "14") (pinfunction "NC_14") (pintype "passive"))
    )
    (net (code "56") (name "unconnected-(U9-NC-Pad15)") (class "Default")
      (node (ref "U9") (pin "15") (pinfunction "NC_15") (pintype "passive"))
    )
    (net (code "57") (name "unconnected-(U10-NC-Pad1)") (class "Default")
      (node (ref "U10") (pin "1") (pinfunction "NC_1") (pintype "passive"))
    )
    (net (code "58") (name "unconnected-(U10-NC-Pad2)") (class "Default")
      (node (ref "U10") (pin "2") (pinfunction "NC_2") (pintype "passive"))
    )
    (net (code "59") (name "unconnected-(U10-NC-Pad7)") (class "Default")
      (node (ref "U10") (pin "7") (pinfunction "NC_7") (pintype "passive"))
    )
    (net (code "60") (name "unconnected-(U10-NC-Pad8)") (class "Default")
      (node (ref "U10") (pin "8") (pinfunction "NC_8") (pintype "passive"))
    )
    (net (code "61") (name "unconnected-(U10-NC-Pad9)") (class "Default")
      (node (ref "U10") (pin "9") (pinfunction "NC_9") (pintype "passive"))
    )
    (net (code "62") (name "unconnected-(U10-NC-Pad10)") (class "Default")
      (node (ref "U10") (pin "10") (pinfunction "NC_10") (pintype "passive"))
    )
    (net (code "63") (name "unconnected-(U10-NC-Pad15)") (class "Default")
      (node (ref "U10") (pin "15") (pinfunction "NC_15") (pintype "passive"))
    )
    (net (code "64") (name "unconnected-(U10-NC-Pad16)") (class "Default")
      (node (ref "U10") (pin "16") (pinfunction "NC_16") (pintype "passive"))
    )
  )
)
